# mimxrt10xx.net
KiCad netlist of a schematic drawn in Altium Designer
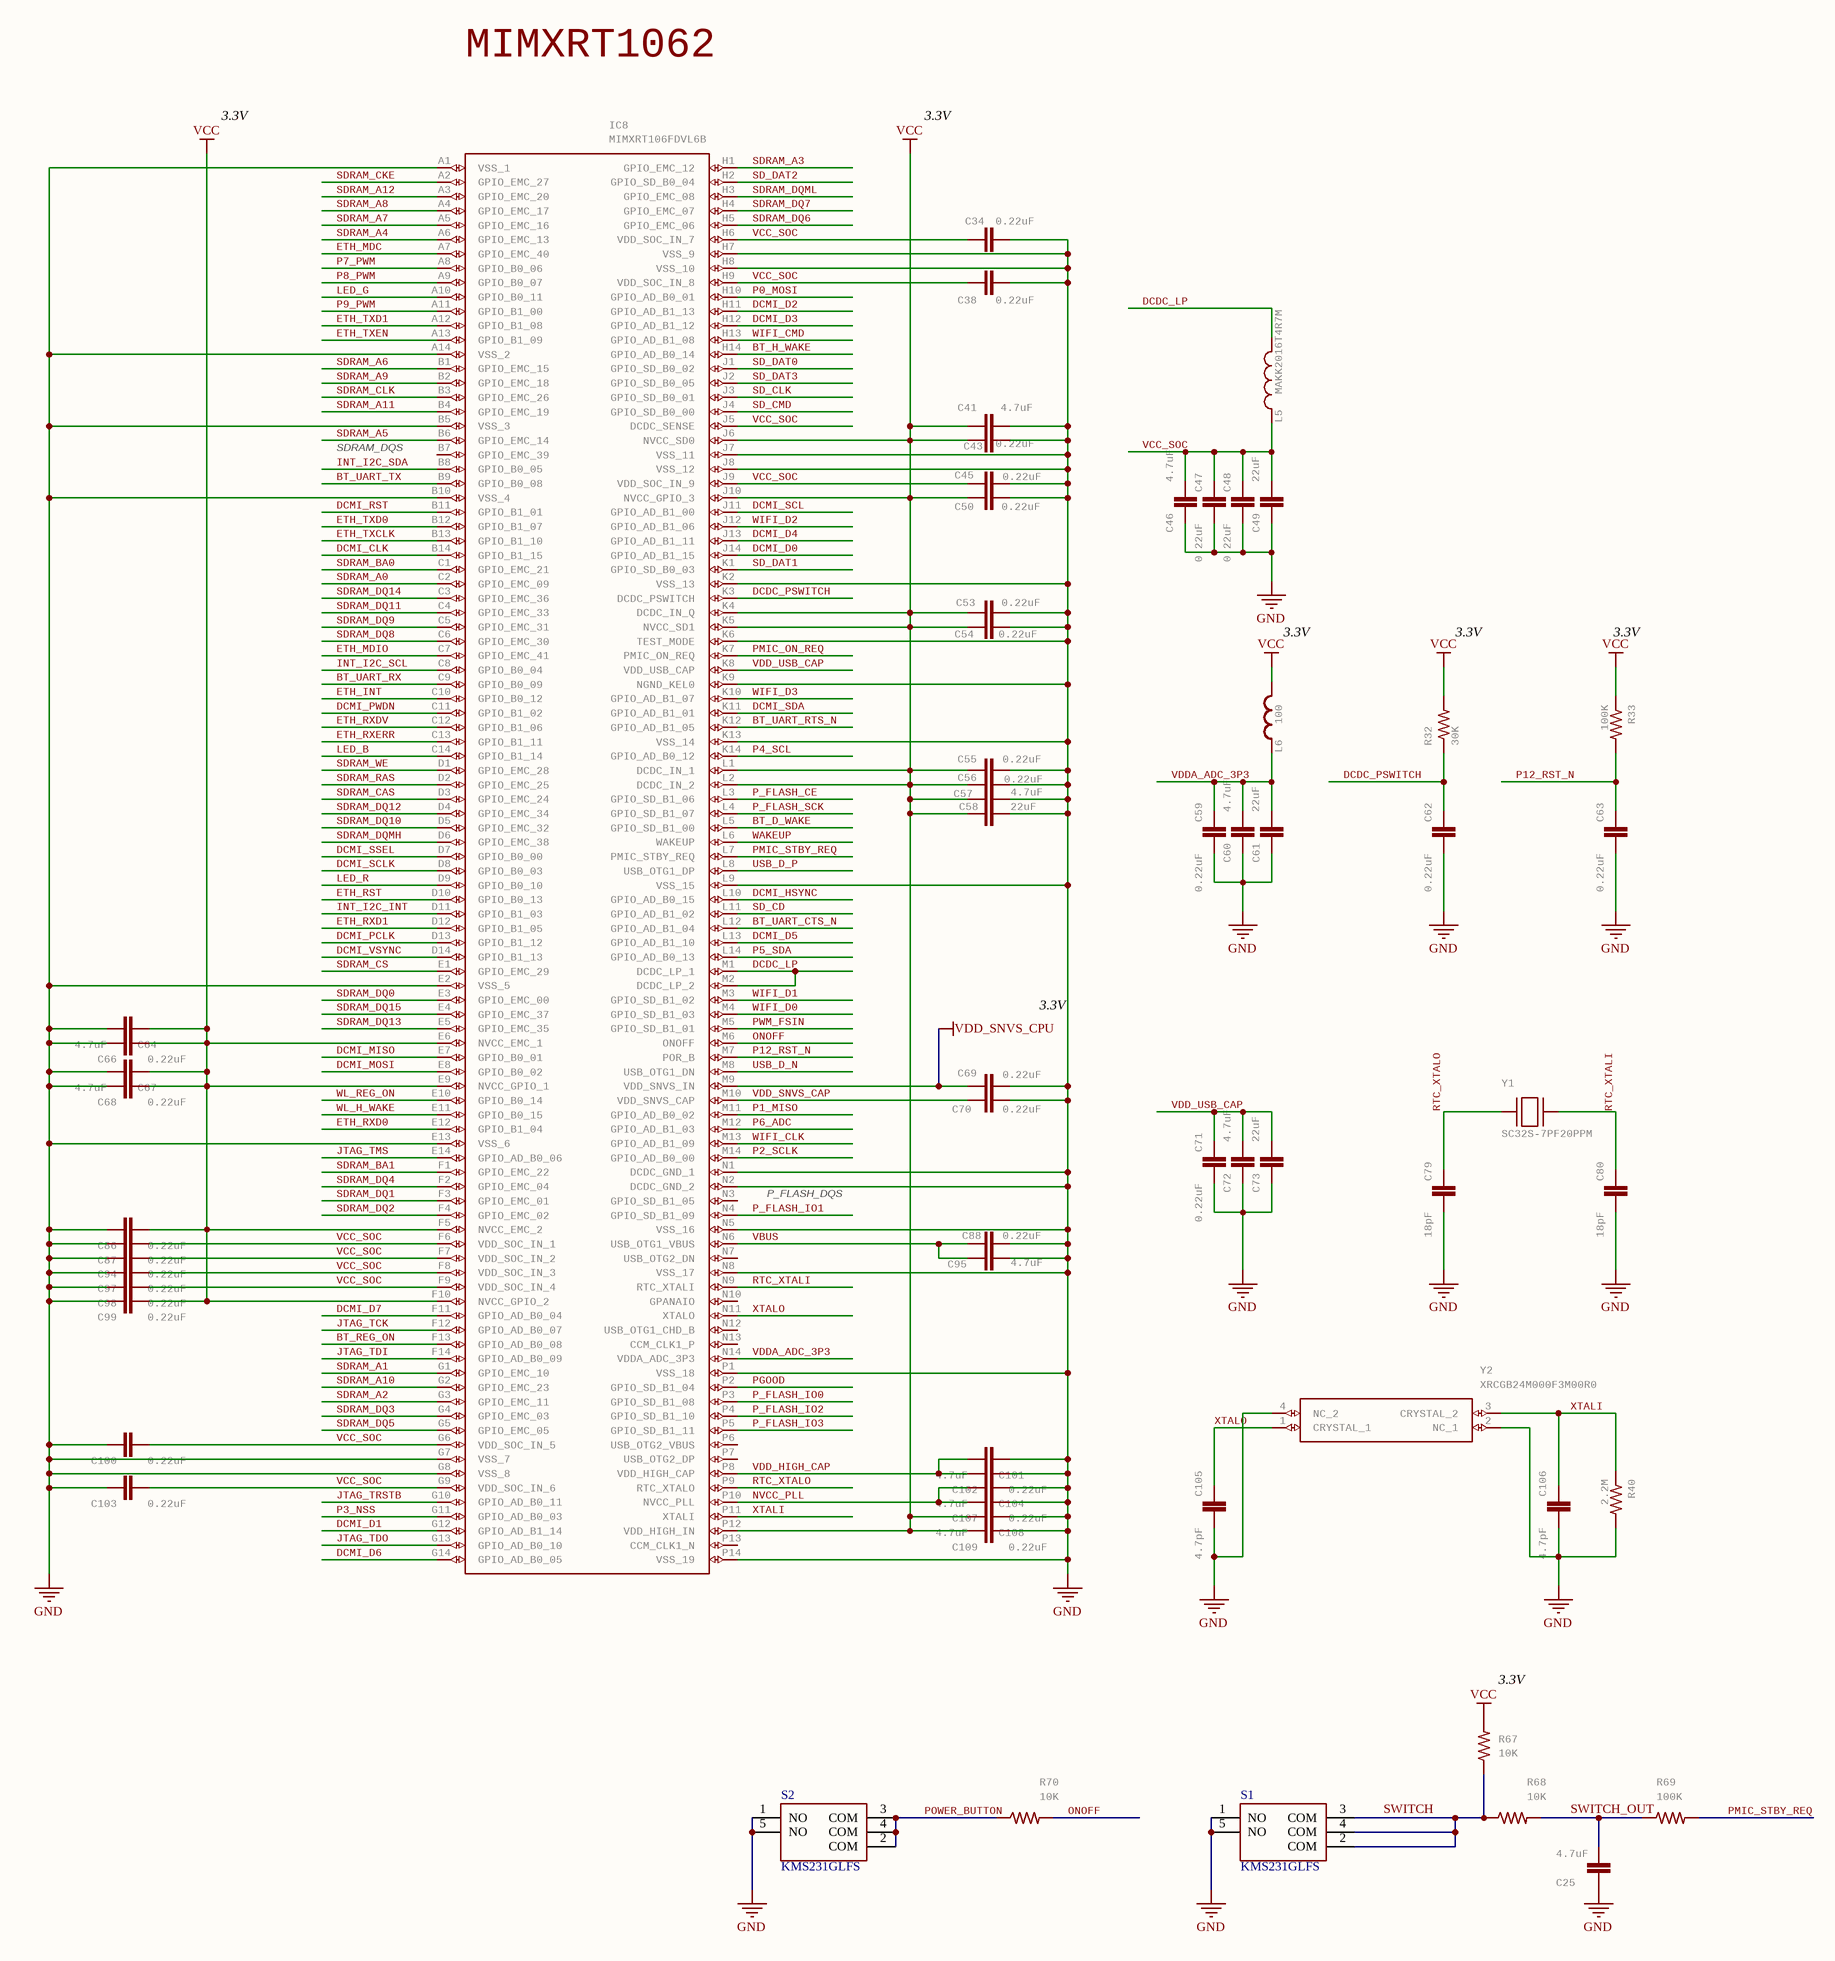
[diagram p0: mimxrt10xx.SchDoc]

(export (version "E")
  (design (tool "Eeschema 10.0.6"))
  (components
    (comp (ref "C25")
      (value "4.7uF")
      (footprint "0402-CAP")
      (description "CapacitorStandard 0603 ceramic capacitor, and 0.1\" leaded capacitor.")
      (fields (field (name "MPN") "JMK105BBJ475MV-F"))
      (libsource (lib "rt10") (part "CAP0402-CAP"))
    )
    (comp (ref "C34")
      (value "0.22uF")
      (footprint "C0201")
      (description "CAPACITOR, European symbol")
      (fields (field (name "MPN") "GRM033R60J224ME15D"))
      (libsource (lib "rt10") (part "C-EUC0201"))
    )
    (comp (ref "C38")
      (value "0.22uF")
      (footprint "C0201")
      (description "CAPACITOR, European symbol")
      (fields (field (name "MPN") "GRM033R60J224ME15D"))
      (libsource (lib "rt10") (part "C-EUC0201"))
    )
    (comp (ref "C41")
      (value "4.7uF")
      (footprint "0402-CAP")
      (description "CapacitorStandard 0603 ceramic capacitor, and 0.1\" leaded capacitor.")
      (fields (field (name "MPN") "JMK105BBJ475MV-F"))
      (libsource (lib "") (part "CAP0402-CAP_1"))
    )
    (comp (ref "C43")
      (value "0.22uF")
      (footprint "C0201")
      (description "CAPACITOR, European symbol")
      (fields (field (name "MPN") "GRM033R60J224ME15D"))
      (libsource (lib "rt10") (part "C-EUC0201"))
    )
    (comp (ref "C45")
      (value "0.22uF")
      (footprint "C0201")
      (description "CAPACITOR, European symbol")
      (fields (field (name "MPN") "GRM033R60J224ME15D"))
      (libsource (lib "rt10") (part "C-EUC0201"))
    )
    (comp (ref "C46")
      (value "4.7uF")
      (footprint "0402-CAP")
      (description "CapacitorStandard 0603 ceramic capacitor, and 0.1\" leaded capacitor.")
      (fields (field (name "MPN") "JMK105BBJ475MV-F"))
      (libsource (lib "rt10") (part "CAP0402-CAP"))
    )
    (comp (ref "C47")
      (value "0.22uF")
      (footprint "C0201")
      (description "CAPACITOR, European symbol")
      (fields (field (name "MPN") "GRM033R60J224ME15D"))
      (libsource (lib "") (part "C-EUC0201_1"))
    )
    (comp (ref "C48")
      (value "0.22uF")
      (footprint "C0201")
      (description "CAPACITOR, European symbol")
      (fields (field (name "MPN") "GRM033R60J224ME15D"))
      (libsource (lib "") (part "C-EUC0201_1"))
    )
    (comp (ref "C49")
      (value "22uF")
      (footprint "0805")
      (fields (field (name "MPN") "CL21A226MQQNNNE"))
      (libsource (lib "rt10") (part "22UF-0805-6.3V-20%"))
    )
    (comp (ref "C50")
      (value "0.22uF")
      (footprint "C0201")
      (description "CAPACITOR, European symbol")
      (fields (field (name "MPN") "GRM033R60J224ME15D"))
      (libsource (lib "rt10") (part "C-EUC0201"))
    )
    (comp (ref "C53")
      (value "0.22uF")
      (footprint "C0201")
      (description "CAPACITOR, European symbol")
      (fields (field (name "MPN") "GRM033R60J224ME15D"))
      (libsource (lib "rt10") (part "C-EUC0201"))
    )
    (comp (ref "C54")
      (value "0.22uF")
      (footprint "C0201")
      (description "CAPACITOR, European symbol")
      (fields (field (name "MPN") "GRM033R60J224ME15D"))
      (libsource (lib "rt10") (part "C-EUC0201"))
    )
    (comp (ref "C55")
      (value "0.22uF")
      (footprint "C0201")
      (description "CAPACITOR, European symbol")
      (fields (field (name "MPN") "GRM033R60J224ME15D"))
      (libsource (lib "rt10") (part "C-EUC0201"))
    )
    (comp (ref "C56")
      (value "0.22uF")
      (footprint "C0201")
      (description "CAPACITOR, European symbol")
      (fields (field (name "MPN") "GRM033R60J224ME15D"))
      (libsource (lib "rt10") (part "C-EUC0201"))
    )
    (comp (ref "C57")
      (value "4.7uF")
      (footprint "0402-CAP")
      (description "CapacitorStandard 0603 ceramic capacitor, and 0.1\" leaded capacitor.")
      (fields (field (name "MPN") "JMK105BBJ475MV-F"))
      (libsource (lib "") (part "CAP0402-CAP_1"))
    )
    (comp (ref "C58")
      (value "22uF")
      (footprint "0805")
      (fields (field (name "MPN") "CL21A226MQQNNNE"))
      (libsource (lib "") (part "22UF-0805-6.3V-20%_1"))
    )
    (comp (ref "C59")
      (value "0.22uF")
      (footprint "C0201")
      (description "CAPACITOR, European symbol")
      (fields (field (name "MPN") "GRM033R60J224ME15D"))
      (libsource (lib "") (part "C-EUC0201_1"))
    )
    (comp (ref "C60")
      (value "4.7uF")
      (footprint "0402-CAP")
      (description "CapacitorStandard 0603 ceramic capacitor, and 0.1\" leaded capacitor.")
      (fields (field (name "MPN") "JMK105BBJ475MV-F"))
      (libsource (lib "rt10") (part "CAP0402-CAP"))
    )
    (comp (ref "C61")
      (value "22uF")
      (footprint "0805")
      (fields (field (name "MPN") "CL21A226MQQNNNE"))
      (libsource (lib "rt10") (part "22UF-0805-6.3V-20%"))
    )
    (comp (ref "C62")
      (value "0.22uF")
      (footprint "C0201")
      (description "CAPACITOR, European symbol")
      (fields (field (name "MPN") "GRM033R60J224ME15D"))
      (libsource (lib "") (part "C-EUC0201_1"))
    )
    (comp (ref "C63")
      (value "0.22uF")
      (footprint "C0201")
      (description "CAPACITOR, European symbol")
      (fields (field (name "MPN") "GRM033R60J224ME15D"))
      (libsource (lib "") (part "C-EUC0201_1"))
    )
    (comp (ref "C64")
      (value "4.7uF")
      (footprint "0402-CAP")
      (description "CapacitorStandard 0603 ceramic capacitor, and 0.1\" leaded capacitor.")
      (fields (field (name "MPN") "JMK105BBJ475MV-F"))
      (libsource (lib "") (part "CAP0402-CAP_1"))
    )
    (comp (ref "C66")
      (value "0.22uF")
      (footprint "C0201")
      (description "CAPACITOR, European symbol")
      (fields (field (name "MPN") "GRM033R60J224ME15D"))
      (libsource (lib "rt10") (part "C-EUC0201"))
    )
    (comp (ref "C67")
      (value "4.7uF")
      (footprint "0402-CAP")
      (description "CapacitorStandard 0603 ceramic capacitor, and 0.1\" leaded capacitor.")
      (fields (field (name "MPN") "JMK105BBJ475MV-F"))
      (libsource (lib "") (part "CAP0402-CAP_1"))
    )
    (comp (ref "C68")
      (value "0.22uF")
      (footprint "C0201")
      (description "CAPACITOR, European symbol")
      (fields (field (name "MPN") "GRM033R60J224ME15D"))
      (libsource (lib "rt10") (part "C-EUC0201"))
    )
    (comp (ref "C69")
      (value "0.22uF")
      (footprint "C0201")
      (description "CAPACITOR, European symbol")
      (fields (field (name "MPN") "GRM033R60J224ME15D"))
      (libsource (lib "rt10") (part "C-EUC0201"))
    )
    (comp (ref "C70")
      (value "0.22uF")
      (footprint "C0201")
      (description "CAPACITOR, European symbol")
      (fields (field (name "MPN") "GRM033R60J224ME15D"))
      (libsource (lib "rt10") (part "C-EUC0201"))
    )
    (comp (ref "C71")
      (value "0.22uF")
      (footprint "C0201")
      (description "CAPACITOR, European symbol")
      (fields (field (name "MPN") "GRM033R60J224ME15D"))
      (libsource (lib "") (part "C-EUC0201_1"))
    )
    (comp (ref "C72")
      (value "4.7uF")
      (footprint "0402-CAP")
      (description "CapacitorStandard 0603 ceramic capacitor, and 0.1\" leaded capacitor.")
      (fields (field (name "MPN") "JMK105BBJ475MV-F"))
      (libsource (lib "rt10") (part "CAP0402-CAP"))
    )
    (comp (ref "C73")
      (value "22uF")
      (footprint "0805")
      (fields (field (name "MPN") "CL21A226MQQNNNE"))
      (libsource (lib "rt10") (part "22UF-0805-6.3V-20%"))
    )
    (comp (ref "C79")
      (value "18pF")
      (footprint "C0201")
      (description "CAPACITOR, European symbol")
      (fields (field (name "MPN") "GRM0335C1E180JA01D"))
      (libsource (lib "") (part "C-EUC0201_1"))
    )
    (comp (ref "C80")
      (value "18pF")
      (footprint "C0201")
      (description "CAPACITOR, European symbol")
      (fields (field (name "MPN") "GRM0335C1E180JA01D"))
      (libsource (lib "") (part "C-EUC0201_1"))
    )
    (comp (ref "C86")
      (value "0.22uF")
      (footprint "C0201")
      (description "CAPACITOR, European symbol")
      (fields (field (name "MPN") "GRM033R60J224ME15D"))
      (libsource (lib "rt10") (part "C-EUC0201"))
    )
    (comp (ref "C87")
      (value "0.22uF")
      (footprint "C0201")
      (description "CAPACITOR, European symbol")
      (fields (field (name "MPN") "GRM033R60J224ME15D"))
      (libsource (lib "rt10") (part "C-EUC0201"))
    )
    (comp (ref "C88")
      (value "0.22uF")
      (footprint "C0201")
      (description "CAPACITOR, European symbol")
      (fields (field (name "MPN") "GRM033R60J224ME15D"))
      (libsource (lib "rt10") (part "C-EUC0201"))
    )
    (comp (ref "C94")
      (value "0.22uF")
      (footprint "C0201")
      (description "CAPACITOR, European symbol")
      (fields (field (name "MPN") "GRM033R60J224ME15D"))
      (libsource (lib "rt10") (part "C-EUC0201"))
    )
    (comp (ref "C95")
      (value "4.7uF")
      (footprint "0402-CAP")
      (description "CapacitorStandard 0603 ceramic capacitor, and 0.1\" leaded capacitor.")
      (fields (field (name "MPN") "JMK105BBJ475MV-F"))
      (libsource (lib "") (part "CAP0402-CAP_1"))
    )
    (comp (ref "C97")
      (value "0.22uF")
      (footprint "C0201")
      (description "CAPACITOR, European symbol")
      (fields (field (name "MPN") "GRM033R60J224ME15D"))
      (libsource (lib "rt10") (part "C-EUC0201"))
    )
    (comp (ref "C98")
      (value "0.22uF")
      (footprint "C0201")
      (description "CAPACITOR, European symbol")
      (fields (field (name "MPN") "GRM033R60J224ME15D"))
      (libsource (lib "rt10") (part "C-EUC0201"))
    )
    (comp (ref "C99")
      (value "0.22uF")
      (footprint "C0201")
      (description "CAPACITOR, European symbol")
      (fields (field (name "MPN") "GRM033R60J224ME15D"))
      (libsource (lib "rt10") (part "C-EUC0201"))
    )
    (comp (ref "C100")
      (value "0.22uF")
      (footprint "C0201")
      (description "CAPACITOR, European symbol")
      (fields (field (name "MPN") "GRM033R60J224ME15D"))
      (libsource (lib "rt10") (part "C-EUC0201"))
    )
    (comp (ref "C101")
      (value "4.7uF")
      (footprint "0402-CAP")
      (description "CapacitorStandard 0603 ceramic capacitor, and 0.1\" leaded capacitor.")
      (fields (field (name "MPN") "JMK105BBJ475MV-F"))
      (libsource (lib "") (part "CAP0402-CAP_1"))
    )
    (comp (ref "C102")
      (value "0.22uF")
      (footprint "C0201")
      (description "CAPACITOR, European symbol")
      (fields (field (name "MPN") "GRM033R60J224ME15D"))
      (libsource (lib "rt10") (part "C-EUC0201"))
    )
    (comp (ref "C103")
      (value "0.22uF")
      (footprint "C0201")
      (description "CAPACITOR, European symbol")
      (fields (field (name "MPN") "GRM033R60J224ME15D"))
      (libsource (lib "rt10") (part "C-EUC0201"))
    )
    (comp (ref "C104")
      (value "4.7uF")
      (footprint "0402-CAP")
      (description "CapacitorStandard 0603 ceramic capacitor, and 0.1\" leaded capacitor.")
      (fields (field (name "MPN") "JMK105BBJ475MV-F"))
      (libsource (lib "") (part "CAP0402-CAP_1"))
    )
    (comp (ref "C105")
      (value "4.7pF")
      (footprint "C0201")
      (description "CAPACITOR, European symbol")
      (fields (field (name "MPN") "GRM0335C1E4R7CA01D"))
      (libsource (lib "") (part "C-EUC0201_1"))
    )
    (comp (ref "C106")
      (value "4.7pF")
      (footprint "C0201")
      (description "CAPACITOR, European symbol")
      (fields (field (name "MPN") "GRM0335C1E4R7CA01D"))
      (libsource (lib "") (part "C-EUC0201_1"))
    )
    (comp (ref "C107")
      (value "0.22uF")
      (footprint "C0201")
      (description "CAPACITOR, European symbol")
      (fields (field (name "MPN") "GRM033R60J224ME15D"))
      (libsource (lib "rt10") (part "C-EUC0201"))
    )
    (comp (ref "C108")
      (value "4.7uF")
      (footprint "0402-CAP")
      (description "CapacitorStandard 0603 ceramic capacitor, and 0.1\" leaded capacitor.")
      (fields (field (name "MPN") "JMK105BBJ475MV-F"))
      (libsource (lib "") (part "CAP0402-CAP_1"))
    )
    (comp (ref "C109")
      (value "0.22uF")
      (footprint "C0201")
      (description "CAPACITOR, European symbol")
      (fields (field (name "MPN") "GRM033R60J224ME15D"))
      (libsource (lib "rt10") (part "C-EUC0201"))
    )
    (comp (ref "IC8")
      (value "MIMXRT106FDVL6B")
      (footprint "BGA196C65P14X14_1000X1000X143")
      (libsource (lib "rt10") (part "MIMXRT1052DVL6B"))
    )
    (comp (ref "L5")
      (value "MAKK2016T4R7M")
      (footprint "INDC2016X100N")
      (description "INDUCTOR, METAL CORE, SHIELDED, SMD HIGH CURRENT, 4.7uH, 20%, TR Check availability")
      (fields (field (name "MF") "Taiyo Yuden"))
      (libsource (lib "rt10") (part "MAKK2016T4R7M"))
    )
    (comp (ref "L6")
      (value "100")
      (footprint "C0402")
      (fields (field (name "MPN") "MFBM1V1005-101-R"))
      (libsource (lib "rt10") (part "INDUCTOR0402"))
    )
    (comp (ref "R32")
      (value "30K")
      (footprint "0201-RES")
      (description "ResistorBasic schematic elements and footprints for 0603, 1206, and PTH resistors.")
      (fields (field (name "MPN") "RC0201FR-0730KL"))
      (libsource (lib "rt10") (part "RESISTOR0402-RES"))
    )
    (comp (ref "R33")
      (value "100K")
      (footprint "0402-RES")
      (description "ResistorBasic schematic elements and footprints for 0603, 1206, and PTH resistors.")
      (fields (field (name "MPN") "AC0402FR-07100KL"))
      (libsource (lib "rt10") (part "RESISTOR0402-RES"))
    )
    (comp (ref "R40")
      (value "2.2M")
      (footprint "0402-RES")
      (description "ResistorBasic schematic elements and footprints for 0603, 1206, and PTH resistors.")
      (fields (field (name "MPN") "RC0402FR-072M2L"))
      (libsource (lib "rt10") (part "RESISTOR0402-RES"))
    )
    (comp (ref "R67")
      (value "10K")
      (footprint "0402-RES")
      (description "ResistorBasic schematic elements and footprints for 0603, 1206, and PTH resistors.")
      (fields (field (name "MPN") "AC0402FR-1310K"))
      (libsource (lib "rt10") (part "RESISTOR0402-RES"))
    )
    (comp (ref "R68")
      (value "10K")
      (footprint "0402-RES")
      (description "ResistorBasic schematic elements and footprints for 0603, 1206, and PTH resistors.")
      (fields (field (name "MPN") "AC0402FR-1310K"))
      (libsource (lib "rt10") (part "RESISTOR0402-RES"))
    )
    (comp (ref "R69")
      (value "100K")
      (footprint "0402-RES")
      (description "ResistorBasic schematic elements and footprints for 0603, 1206, and PTH resistors.")
      (fields (field (name "MPN") "AC0402FR-07100KL"))
      (libsource (lib "rt10") (part "RESISTOR0402-RES"))
    )
    (comp (ref "R70")
      (value "10K")
      (footprint "0402-RES")
      (description "ResistorBasic schematic elements and footprints for 0603, 1206, and PTH resistors.")
      (fields (field (name "MPN") "AC0402FR-1310K"))
      (libsource (lib "rt10") (part "RESISTOR0402-RES"))
    )
    (comp (ref "S1")
      (value "KMS231GLFS")
      (footprint "KMS231GLFS")
      (libsource (lib "rt10") (part "KMS231GLFS"))
    )
    (comp (ref "S2")
      (value "KMS231GLFS")
      (footprint "KMS231GLFS")
      (libsource (lib "rt10") (part "KMS231GLFS"))
    )
    (comp (ref "Y1")
      (value "SC32S-7PF20PPM")
      (footprint "XTAL_ABS07-32.768KHZ-7-T")
      (description "Check availability")
      (fields (field (name "MF") "Abracon") (field (name "MP") "ABS07-32.768KHZ-7-T"))
      (libsource (lib "rt10") (part "ABS07-32.768KHZ-7-T"))
    )
    (comp (ref "Y2")
      (value "XRCGB24M000F3M00R0")
      (footprint "XRCGB24M000F3M00R0")
      (description "Murata 24MHz Crystal +/-30ppm SMD 4-Pin 2 x 1.6 x 0.7mm   Source:  Datasheet")
      (fields (field (name "MOUSER_PART_NUMBER") "81-XRCGB24M000F3M0R0"))
      (libsource (lib "rt10") (part "XRCGB24M000F3M00R0"))
    )
  )
  (nets
    (net (code "1") (name "/BT_D_WAKE") (class "Default")
      (node (ref "IC8") (pin "L5") (pinfunction "GPIO_SD_B1_00_L5") (pintype "bidirectional"))
    )
    (net (code "2") (name "/BT_H_WAKE") (class "Default")
      (node (ref "IC8") (pin "H14") (pinfunction "GPIO_AD_B0_14_H14") (pintype "bidirectional"))
    )
    (net (code "3") (name "/BT_REG_ON") (class "Default")
      (node (ref "IC8") (pin "F13") (pinfunction "GPIO_AD_B0_08_F13") (pintype "bidirectional"))
    )
    (net (code "4") (name "/BT_UART_CTS_N") (class "Default")
      (node (ref "IC8") (pin "L12") (pinfunction "GPIO_AD_B1_04_L12") (pintype "bidirectional"))
    )
    (net (code "5") (name "/BT_UART_RTS_N") (class "Default")
      (node (ref "IC8") (pin "K12") (pinfunction "GPIO_AD_B1_05_K12") (pintype "bidirectional"))
    )
    (net (code "6") (name "/BT_UART_RX") (class "Default")
      (node (ref "IC8") (pin "C9") (pinfunction "GPIO_B0_09_C9") (pintype "bidirectional"))
    )
    (net (code "7") (name "/BT_UART_TX") (class "Default")
      (node (ref "IC8") (pin "B9") (pinfunction "GPIO_B0_08_B9") (pintype "bidirectional"))
    )
    (net (code "8") (name "/DCDC_LP") (class "Default")
      (node (ref "IC8") (pin "M1") (pinfunction "DCDC_LP_1_M1") (pintype "bidirectional"))
      (node (ref "IC8") (pin "M2") (pinfunction "DCDC_LP_2_M2") (pintype "bidirectional"))
      (node (ref "L5") (pin "2") (pinfunction "2_2") (pintype "passive"))
    )
    (net (code "9") (name "/DCDC_PSWITCH") (class "Default")
      (node (ref "C62") (pin "1") (pinfunction "1_1") (pintype "passive"))
      (node (ref "IC8") (pin "K3") (pinfunction "DCDC_PSWITCH_K3") (pintype "bidirectional"))
      (node (ref "R32") (pin "1") (pinfunction "1_1") (pintype "passive"))
    )
    (net (code "10") (name "/DCMI_CLK") (class "Default")
      (node (ref "IC8") (pin "B14") (pinfunction "GPIO_B1_15_B14") (pintype "bidirectional"))
    )
    (net (code "11") (name "/DCMI_D0") (class "Default")
      (node (ref "IC8") (pin "J14") (pinfunction "GPIO_AD_B1_15_J14") (pintype "bidirectional"))
    )
    (net (code "12") (name "/DCMI_D1") (class "Default")
      (node (ref "IC8") (pin "G12") (pinfunction "GPIO_AD_B1_14_G12") (pintype "bidirectional"))
    )
    (net (code "13") (name "/DCMI_D2") (class "Default")
      (node (ref "IC8") (pin "H11") (pinfunction "GPIO_AD_B1_13_H11") (pintype "bidirectional"))
    )
    (net (code "14") (name "/DCMI_D3") (class "Default")
      (node (ref "IC8") (pin "H12") (pinfunction "GPIO_AD_B1_12_H12") (pintype "bidirectional"))
    )
    (net (code "15") (name "/DCMI_D4") (class "Default")
      (node (ref "IC8") (pin "J13") (pinfunction "GPIO_AD_B1_11_J13") (pintype "bidirectional"))
    )
    (net (code "16") (name "/DCMI_D5") (class "Default")
      (node (ref "IC8") (pin "L13") (pinfunction "GPIO_AD_B1_10_L13") (pintype "bidirectional"))
    )
    (net (code "17") (name "/DCMI_D6") (class "Default")
      (node (ref "IC8") (pin "G14") (pinfunction "GPIO_AD_B0_05_G14") (pintype "bidirectional"))
    )
    (net (code "18") (name "/DCMI_D7") (class "Default")
      (node (ref "IC8") (pin "F11") (pinfunction "GPIO_AD_B0_04_F11") (pintype "bidirectional"))
    )
    (net (code "19") (name "/DCMI_HSYNC") (class "Default")
      (node (ref "IC8") (pin "L10") (pinfunction "GPIO_AD_B0_15_L10") (pintype "bidirectional"))
    )
    (net (code "20") (name "/DCMI_MISO") (class "Default")
      (node (ref "IC8") (pin "E7") (pinfunction "GPIO_B0_01_E7") (pintype "bidirectional"))
    )
    (net (code "21") (name "/DCMI_MOSI") (class "Default")
      (node (ref "IC8") (pin "E8") (pinfunction "GPIO_B0_02_E8") (pintype "bidirectional"))
    )
    (net (code "22") (name "/DCMI_PCLK") (class "Default")
      (node (ref "IC8") (pin "D13") (pinfunction "GPIO_B1_12_D13") (pintype "bidirectional"))
    )
    (net (code "23") (name "/DCMI_PWDN") (class "Default")
      (node (ref "IC8") (pin "C11") (pinfunction "GPIO_B1_02_C11") (pintype "bidirectional"))
    )
    (net (code "24") (name "/DCMI_RST") (class "Default")
      (node (ref "IC8") (pin "B11") (pinfunction "GPIO_B1_01_B11") (pintype "bidirectional"))
    )
    (net (code "25") (name "/DCMI_SCL") (class "Default")
      (node (ref "IC8") (pin "J11") (pinfunction "GPIO_AD_B1_00_J11") (pintype "bidirectional"))
    )
    (net (code "26") (name "/DCMI_SCLK") (class "Default")
      (node (ref "IC8") (pin "D8") (pinfunction "GPIO_B0_03_D8") (pintype "bidirectional"))
    )
    (net (code "27") (name "/DCMI_SDA") (class "Default")
      (node (ref "IC8") (pin "K11") (pinfunction "GPIO_AD_B1_01_K11") (pintype "bidirectional"))
    )
    (net (code "28") (name "/DCMI_SSEL") (class "Default")
      (node (ref "IC8") (pin "D7") (pinfunction "GPIO_B0_00_D7") (pintype "bidirectional"))
    )
    (net (code "29") (name "/DCMI_VSYNC") (class "Default")
      (node (ref "IC8") (pin "D14") (pinfunction "GPIO_B1_13_D14") (pintype "bidirectional"))
    )
    (net (code "30") (name "/ETH_INT") (class "Default")
      (node (ref "IC8") (pin "C10") (pinfunction "GPIO_B0_12_C10") (pintype "bidirectional"))
    )
    (net (code "31") (name "/ETH_MDC") (class "Default")
      (node (ref "IC8") (pin "A7") (pinfunction "GPIO_EMC_40_A7") (pintype "bidirectional"))
    )
    (net (code "32") (name "/ETH_MDIO") (class "Default")
      (node (ref "IC8") (pin "C7") (pinfunction "GPIO_EMC_41_C7") (pintype "bidirectional"))
    )
    (net (code "33") (name "/ETH_RST") (class "Default")
      (node (ref "IC8") (pin "D10") (pinfunction "GPIO_B0_13_D10") (pintype "bidirectional"))
    )
    (net (code "34") (name "/ETH_RXD0") (class "Default")
      (node (ref "IC8") (pin "E12") (pinfunction "GPIO_B1_04_E12") (pintype "bidirectional"))
    )
    (net (code "35") (name "/ETH_RXD1") (class "Default")
      (node (ref "IC8") (pin "D12") (pinfunction "GPIO_B1_05_D12") (pintype "bidirectional"))
    )
    (net (code "36") (name "/ETH_RXDV") (class "Default")
      (node (ref "IC8") (pin "C12") (pinfunction "GPIO_B1_06_C12") (pintype "bidirectional"))
    )
    (net (code "37") (name "/ETH_RXERR") (class "Default")
      (node (ref "IC8") (pin "C13") (pinfunction "GPIO_B1_11_C13") (pintype "bidirectional"))
    )
    (net (code "38") (name "/ETH_TXCLK") (class "Default")
      (node (ref "IC8") (pin "B13") (pinfunction "GPIO_B1_10_B13") (pintype "bidirectional"))
    )
    (net (code "39") (name "/ETH_TXD0") (class "Default")
      (node (ref "IC8") (pin "B12") (pinfunction "GPIO_B1_07_B12") (pintype "bidirectional"))
    )
    (net (code "40") (name "/ETH_TXD1") (class "Default")
      (node (ref "IC8") (pin "A12") (pinfunction "GPIO_B1_08_A12") (pintype "bidirectional"))
    )
    (net (code "41") (name "/ETH_TXEN") (class "Default")
      (node (ref "IC8") (pin "A13") (pinfunction "GPIO_B1_09_A13") (pintype "bidirectional"))
    )
    (net (code "42") (name "/INT_I2C_INT") (class "Default")
      (node (ref "IC8") (pin "D11") (pinfunction "GPIO_B1_03_D11") (pintype "bidirectional"))
    )
    (net (code "43") (name "/INT_I2C_SCL") (class "Default")
      (node (ref "IC8") (pin "C8") (pinfunction "GPIO_B0_04_C8") (pintype "bidirectional"))
    )
    (net (code "44") (name "/INT_I2C_SDA") (class "Default")
      (node (ref "IC8") (pin "B8") (pinfunction "GPIO_B0_05_B8") (pintype "bidirectional"))
    )
    (net (code "45") (name "/JTAG_TCK") (class "Default")
      (node (ref "IC8") (pin "F12") (pinfunction "GPIO_AD_B0_07_F12") (pintype "bidirectional"))
    )
    (net (code "46") (name "/JTAG_TDI") (class "Default")
      (node (ref "IC8") (pin "F14") (pinfunction "GPIO_AD_B0_09_F14") (pintype "bidirectional"))
    )
    (net (code "47") (name "/JTAG_TDO") (class "Default")
      (node (ref "IC8") (pin "G13") (pinfunction "GPIO_AD_B0_10_G13") (pintype "bidirectional"))
    )
    (net (code "48") (name "/JTAG_TMS") (class "Default")
      (node (ref "IC8") (pin "E14") (pinfunction "GPIO_AD_B0_06_E14") (pintype "bidirectional"))
    )
    (net (code "49") (name "/JTAG_TRSTB") (class "Default")
      (node (ref "IC8") (pin "G10") (pinfunction "GPIO_AD_B0_11_G10") (pintype "bidirectional"))
    )
    (net (code "50") (name "/LED_B") (class "Default")
      (node (ref "IC8") (pin "C14") (pinfunction "GPIO_B1_14_C14") (pintype "bidirectional"))
    )
    (net (code "51") (name "/LED_G") (class "Default")
      (node (ref "IC8") (pin "A10") (pinfunction "GPIO_B0_11_A10") (pintype "bidirectional"))
    )
    (net (code "52") (name "/LED_R") (class "Default")
      (node (ref "IC8") (pin "D9") (pinfunction "GPIO_B0_10_D9") (pintype "bidirectional"))
    )
    (net (code "53") (name "/NVCC_PLL") (class "Default")
      (node (ref "C104") (pin "2") (pinfunction "2_2") (pintype "passive"))
      (node (ref "C107") (pin "1") (pinfunction "1_1") (pintype "passive"))
      (node (ref "IC8") (pin "P10") (pinfunction "NVCC_PLL_P10") (pintype "bidirectional"))
    )
    (net (code "54") (name "/ONOFF") (class "Default")
      (node (ref "IC8") (pin "M6") (pinfunction "ONOFF_M6") (pintype "bidirectional"))
      (node (ref "R70") (pin "2") (pinfunction "2_2") (pintype "passive"))
    )
    (net (code "55") (name "/P0_MOSI") (class "Default")
      (node (ref "IC8") (pin "H10") (pinfunction "GPIO_AD_B0_01_H10") (pintype "bidirectional"))
    )
    (net (code "56") (name "/P1_MISO") (class "Default")
      (node (ref "IC8") (pin "M11") (pinfunction "GPIO_AD_B0_02_M11") (pintype "bidirectional"))
    )
    (net (code "57") (name "/P2_SCLK") (class "Default")
      (node (ref "IC8") (pin "M14") (pinfunction "GPIO_AD_B0_00_M14") (pintype "bidirectional"))
    )
    (net (code "58") (name "/P3_NSS") (class "Default")
      (node (ref "IC8") (pin "G11") (pinfunction "GPIO_AD_B0_03_G11") (pintype "bidirectional"))
    )
    (net (code "59") (name "/P4_SCL") (class "Default")
      (node (ref "IC8") (pin "K14") (pinfunction "GPIO_AD_B0_12_K14") (pintype "bidirectional"))
    )
    (net (code "60") (name "/P5_SDA") (class "Default")
      (node (ref "IC8") (pin "L14") (pinfunction "GPIO_AD_B0_13_L14") (pintype "bidirectional"))
    )
    (net (code "61") (name "/P6_ADC") (class "Default")
      (node (ref "IC8") (pin "M12") (pinfunction "GPIO_AD_B1_03_M12") (pintype "bidirectional"))
    )
    (net (code "62") (name "/P7_PWM") (class "Default")
      (node (ref "IC8") (pin "A8") (pinfunction "GPIO_B0_06_A8") (pintype "bidirectional"))
    )
    (net (code "63") (name "/P8_PWM") (class "Default")
      (node (ref "IC8") (pin "A9") (pinfunction "GPIO_B0_07_A9") (pintype "bidirectional"))
    )
    (net (code "64") (name "/P9_PWM") (class "Default")
      (node (ref "IC8") (pin "A11") (pinfunction "GPIO_B1_00_A11") (pintype "bidirectional"))
    )
    (net (code "65") (name "/P12_RST_N") (class "Default")
      (node (ref "C63") (pin "1") (pinfunction "1_1") (pintype "passive"))
      (node (ref "IC8") (pin "M7") (pinfunction "POR_B_M7") (pintype "bidirectional"))
      (node (ref "R33") (pin "2") (pinfunction "2_2") (pintype "passive"))
    )
    (net (code "66") (name "/PGOOD") (class "Default")
      (node (ref "IC8") (pin "P2") (pinfunction "GPIO_SD_B1_04_P2") (pintype "bidirectional"))
    )
    (net (code "67") (name "/PMIC_ON_REQ") (class "Default")
      (node (ref "IC8") (pin "K7") (pinfunction "PMIC_ON_REQ_K7") (pintype "bidirectional"))
    )
    (net (code "68") (name "/PMIC_STBY_REQ") (class "Default")
      (node (ref "IC8") (pin "L7") (pinfunction "PMIC_STBY_REQ_L7") (pintype "bidirectional"))
      (node (ref "R69") (pin "2") (pinfunction "2_2") (pintype "passive"))
    )
    (net (code "69") (name "/POWER_BUTTON") (class "Default")
      (node (ref "R70") (pin "1") (pinfunction "1_1") (pintype "passive"))
      (node (ref "S2") (pin "2") (pinfunction "COM_2") (pintype "passive"))
      (node (ref "S2") (pin "3") (pinfunction "COM_3") (pintype "passive"))
      (node (ref "S2") (pin "4") (pinfunction "COM_4") (pintype "passive"))
    )
    (net (code "70") (name "/PWM_FSIN") (class "Default")
      (node (ref "IC8") (pin "M5") (pinfunction "GPIO_SD_B1_01_M5") (pintype "bidirectional"))
    )
    (net (code "71") (name "/P_FLASH_CE") (class "Default")
      (node (ref "IC8") (pin "L3") (pinfunction "GPIO_SD_B1_06_L3") (pintype "bidirectional"))
    )
    (net (code "72") (name "/P_FLASH_IO0") (class "Default")
      (node (ref "IC8") (pin "P3") (pinfunction "GPIO_SD_B1_08_P3") (pintype "bidirectional"))
    )
    (net (code "73") (name "/P_FLASH_IO1") (class "Default")
      (node (ref "IC8") (pin "N4") (pinfunction "GPIO_SD_B1_09_N4") (pintype "bidirectional"))
    )
    (net (code "74") (name "/P_FLASH_IO2") (class "Default")
      (node (ref "IC8") (pin "P4") (pinfunction "GPIO_SD_B1_10_P4") (pintype "bidirectional"))
    )
    (net (code "75") (name "/P_FLASH_IO3") (class "Default")
      (node (ref "IC8") (pin "P5") (pinfunction "GPIO_SD_B1_11_P5") (pintype "bidirectional"))
    )
    (net (code "76") (name "/P_FLASH_SCK") (class "Default")
      (node (ref "IC8") (pin "L4") (pinfunction "GPIO_SD_B1_07_L4") (pintype "bidirectional"))
    )
    (net (code "77") (name "/RTC_XTALI") (class "Default")
      (node (ref "C80") (pin "1") (pinfunction "1_1") (pintype "passive"))
      (node (ref "IC8") (pin "N9") (pinfunction "RTC_XTALI_N9") (pintype "bidirectional"))
      (node (ref "Y1") (pin "2") (pinfunction "2_2") (pintype "passive"))
    )
    (net (code "78") (name "/RTC_XTALO") (class "Default")
      (node (ref "C79") (pin "1") (pinfunction "1_1") (pintype "passive"))
      (node (ref "IC8") (pin "P9") (pinfunction "RTC_XTALO_P9") (pintype "bidirectional"))
      (node (ref "Y1") (pin "1") (pinfunction "1_1") (pintype "passive"))
    )
    (net (code "79") (name "/SDRAM_A0") (class "Default")
      (node (ref "IC8") (pin "C2") (pinfunction "GPIO_EMC_09_C2") (pintype "bidirectional"))
    )
    (net (code "80") (name "/SDRAM_A1") (class "Default")
      (node (ref "IC8") (pin "G1") (pinfunction "GPIO_EMC_10_G1") (pintype "bidirectional"))
    )
    (net (code "81") (name "/SDRAM_A2") (class "Default")
      (node (ref "IC8") (pin "G3") (pinfunction "GPIO_EMC_11_G3") (pintype "bidirectional"))
    )
    (net (code "82") (name "/SDRAM_A3") (class "Default")
      (node (ref "IC8") (pin "H1") (pinfunction "GPIO_EMC_12_H1") (pintype "bidirectional"))
    )
    (net (code "83") (name "/SDRAM_A4") (class "Default")
      (node (ref "IC8") (pin "A6") (pinfunction "GPIO_EMC_13_A6") (pintype "bidirectional"))
    )
    (net (code "84") (name "/SDRAM_A5") (class "Default")
      (node (ref "IC8") (pin "B6") (pinfunction "GPIO_EMC_14_B6") (pintype "bidirectional"))
    )
    (net (code "85") (name "/SDRAM_A6") (class "Default")
      (node (ref "IC8") (pin "B1") (pinfunction "GPIO_EMC_15_B1") (pintype "bidirectional"))
    )
    (net (code "86") (name "/SDRAM_A7") (class "Default")
      (node (ref "IC8") (pin "A5") (pinfunction "GPIO_EMC_16_A5") (pintype "bidirectional"))
    )
    (net (code "87") (name "/SDRAM_A8") (class "Default")
      (node (ref "IC8") (pin "A4") (pinfunction "GPIO_EMC_17_A4") (pintype "bidirectional"))
    )
    (net (code "88") (name "/SDRAM_A9") (class "Default")
      (node (ref "IC8") (pin "B2") (pinfunction "GPIO_EMC_18_B2") (pintype "bidirectional"))
    )
    (net (code "89") (name "/SDRAM_A10") (class "Default")
      (node (ref "IC8") (pin "G2") (pinfunction "GPIO_EMC_23_G2") (pintype "bidirectional"))
    )
    (net (code "90") (name "/SDRAM_A11") (class "Default")
      (node (ref "IC8") (pin "B4") (pinfunction "GPIO_EMC_19_B4") (pintype "bidirectional"))
    )
    (net (code "91") (name "/SDRAM_A12") (class "Default")
      (node (ref "IC8") (pin "A3") (pinfunction "GPIO_EMC_20_A3") (pintype "bidirectional"))
    )
    (net (code "92") (name "/SDRAM_BA0") (class "Default")
      (node (ref "IC8") (pin "C1") (pinfunction "GPIO_EMC_21_C1") (pintype "bidirectional"))
    )
    (net (code "93") (name "/SDRAM_BA1") (class "Default")
      (node (ref "IC8") (pin "F1") (pinfunction "GPIO_EMC_22_F1") (pintype "bidirectional"))
    )
    (net (code "94") (name "/SDRAM_CAS") (class "Default")
      (node (ref "IC8") (pin "D3") (pinfunction "GPIO_EMC_24_D3") (pintype "bidirectional"))
    )
    (net (code "95") (name "/SDRAM_CKE") (class "Default")
      (node (ref "IC8") (pin "A2") (pinfunction "GPIO_EMC_27_A2") (pintype "bidirectional"))
    )
    (net (code "96") (name "/SDRAM_CLK") (class "Default")
      (node (ref "IC8") (pin "B3") (pinfunction "GPIO_EMC_26_B3") (pintype "bidirectional"))
    )
    (net (code "97") (name "/SDRAM_CS") (class "Default")
      (node (ref "IC8") (pin "E1") (pinfunction "GPIO_EMC_29_E1") (pintype "bidirectional"))
    )
    (net (code "98") (name "/SDRAM_DQ0") (class "Default")
      (node (ref "IC8") (pin "E3") (pinfunction "GPIO_EMC_00_E3") (pintype "bidirectional"))
    )
    (net (code "99") (name "/SDRAM_DQ1") (class "Default")
      (node (ref "IC8") (pin "F3") (pinfunction "GPIO_EMC_01_F3") (pintype "bidirectional"))
    )
    (net (code "100") (name "/SDRAM_DQ2") (class "Default")
      (node (ref "IC8") (pin "F4") (pinfunction "GPIO_EMC_02_F4") (pintype "bidirectional"))
    )
    (net (code "101") (name "/SDRAM_DQ3") (class "Default")
      (node (ref "IC8") (pin "G4") (pinfunction "GPIO_EMC_03_G4") (pintype "bidirectional"))
    )
    (net (code "102") (name "/SDRAM_DQ4") (class "Default")
      (node (ref "IC8") (pin "F2") (pinfunction "GPIO_EMC_04_F2") (pintype "bidirectional"))
    )
    (net (code "103") (name "/SDRAM_DQ5") (class "Default")
      (node (ref "IC8") (pin "G5") (pinfunction "GPIO_EMC_05_G5") (pintype "bidirectional"))
    )
    (net (code "104") (name "/SDRAM_DQ6") (class "Default")
      (node (ref "IC8") (pin "H5") (pinfunction "GPIO_EMC_06_H5") (pintype "bidirectional"))
    )
    (net (code "105") (name "/SDRAM_DQ7") (class "Default")
      (node (ref "IC8") (pin "H4") (pinfunction "GPIO_EMC_07_H4") (pintype "bidirectional"))
    )
    (net (code "106") (name "/SDRAM_DQ8") (class "Default")
      (node (ref "IC8") (pin "C6") (pinfunction "GPIO_EMC_30_C6") (pintype "bidirectional"))
    )
    (net (code "107") (name "/SDRAM_DQ9") (class "Default")
      (node (ref "IC8") (pin "C5") (pinfunction "GPIO_EMC_31_C5") (pintype "bidirectional"))
    )
    (net (code "108") (name "/SDRAM_DQ10") (class "Default")
      (node (ref "IC8") (pin "D5") (pinfunction "GPIO_EMC_32_D5") (pintype "bidirectional"))
    )
    (net (code "109") (name "/SDRAM_DQ11") (class "Default")
      (node (ref "IC8") (pin "C4") (pinfunction "GPIO_EMC_33_C4") (pintype "bidirectional"))
    )
    (net (code "110") (name "/SDRAM_DQ12") (class "Default")
      (node (ref "IC8") (pin "D4") (pinfunction "GPIO_EMC_34_D4") (pintype "bidirectional"))
    )
    (net (code "111") (name "/SDRAM_DQ13") (class "Default")
      (node (ref "IC8") (pin "E5") (pinfunction "GPIO_EMC_35_E5") (pintype "bidirectional"))
    )
    (net (code "112") (name "/SDRAM_DQ14") (class "Default")
      (node (ref "IC8") (pin "C3") (pinfunction "GPIO_EMC_36_C3") (pintype "bidirectional"))
    )
    (net (code "113") (name "/SDRAM_DQ15") (class "Default")
      (node (ref "IC8") (pin "E4") (pinfunction "GPIO_EMC_37_E4") (pintype "bidirectional"))
    )
    (net (code "114") (name "/SDRAM_DQMH") (class "Default")
      (node (ref "IC8") (pin "D6") (pinfunction "GPIO_EMC_38_D6") (pintype "bidirectional"))
    )
    (net (code "115") (name "/SDRAM_DQML") (class "Default")
      (node (ref "IC8") (pin "H3") (pinfunction "GPIO_EMC_08_H3") (pintype "bidirectional"))
    )
    (net (code "116") (name "/SDRAM_RAS") (class "Default")
      (node (ref "IC8") (pin "D2") (pinfunction "GPIO_EMC_25_D2") (pintype "bidirectional"))
    )
    (net (code "117") (name "/SDRAM_WE") (class "Default")
      (node (ref "IC8") (pin "D1") (pinfunction "GPIO_EMC_28_D1") (pintype "bidirectional"))
    )
    (net (code "118") (name "/SD_CD") (class "Default")
      (node (ref "IC8") (pin "L11") (pinfunction "GPIO_AD_B1_02_L11") (pintype "bidirectional"))
    )
    (net (code "119") (name "/SD_CLK") (class "Default")
      (node (ref "IC8") (pin "J3") (pinfunction "GPIO_SD_B0_01_J3") (pintype "bidirectional"))
    )
    (net (code "120") (name "/SD_CMD") (class "Default")
      (node (ref "IC8") (pin "J4") (pinfunction "GPIO_SD_B0_00_J4") (pintype "bidirectional"))
    )
    (net (code "121") (name "/SD_DAT0") (class "Default")
      (node (ref "IC8") (pin "J1") (pinfunction "GPIO_SD_B0_02_J1") (pintype "bidirectional"))
    )
    (net (code "122") (name "/SD_DAT1") (class "Default")
      (node (ref "IC8") (pin "K1") (pinfunction "GPIO_SD_B0_03_K1") (pintype "bidirectional"))
    )
    (net (code "123") (name "/SD_DAT2") (class "Default")
      (node (ref "IC8") (pin "H2") (pinfunction "GPIO_SD_B0_04_H2") (pintype "bidirectional"))
    )
    (net (code "124") (name "/SD_DAT3") (class "Default")
      (node (ref "IC8") (pin "J2") (pinfunction "GPIO_SD_B0_05_J2") (pintype "bidirectional"))
    )
    (net (code "125") (name "/SWITCH") (class "Default")
      (node (ref "R67") (pin "1") (pinfunction "1_1") (pintype "passive"))
      (node (ref "R68") (pin "1") (pinfunction "1_1") (pintype "passive"))
      (node (ref "S1") (pin "2") (pinfunction "COM_2") (pintype "passive"))
      (node (ref "S1") (pin "3") (pinfunction "COM_3") (pintype "passive"))
      (node (ref "S1") (pin "4") (pinfunction "COM_4") (pintype "passive"))
    )
    (net (code "126") (name "/SWITCH_OUT") (class "Default")
      (node (ref "C25") (pin "2") (pinfunction "2_2") (pintype "passive"))
      (node (ref "R68") (pin "2") (pinfunction "2_2") (pintype "passive"))
      (node (ref "R69") (pin "1") (pinfunction "1_1") (pintype "passive"))
    )
    (net (code "127") (name "/USB_D_N") (class "Default")
      (node (ref "IC8") (pin "M8") (pinfunction "USB_OTG1_DN_M8") (pintype "bidirectional"))
    )
    (net (code "128") (name "/USB_D_P") (class "Default")
      (node (ref "IC8") (pin "L8") (pinfunction "USB_OTG1_DP_L8") (pintype "bidirectional"))
    )
    (net (code "129") (name "/VBUS") (class "Default")
      (node (ref "C88") (pin "1") (pinfunction "1_1") (pintype "passive"))
      (node (ref "C95") (pin "2") (pinfunction "2_2") (pintype "passive"))
      (node (ref "IC8") (pin "N6") (pinfunction "USB_OTG1_VBUS_N6") (pintype "bidirectional"))
    )
    (net (code "130") (name "/VCC_SOC") (class "Default")
      (node (ref "C100") (pin "2") (pinfunction "2_2") (pintype "passive"))
      (node (ref "C103") (pin "2") (pinfunction "2_2") (pintype "passive"))
      (node (ref "C34") (pin "1") (pinfunction "1_1") (pintype "passive"))
      (node (ref "C38") (pin "1") (pinfunction "1_1") (pintype "passive"))
      (node (ref "C45") (pin "1") (pinfunction "1_1") (pintype "passive"))
      (node (ref "C46") (pin "2") (pinfunction "2_2") (pintype "passive"))
      (node (ref "C47") (pin "1") (pinfunction "1_1") (pintype "passive"))
      (node (ref "C48") (pin "1") (pinfunction "1_1") (pintype "passive"))
      (node (ref "C49") (pin "2") (pinfunction "2_2") (pintype "passive"))
      (node (ref "C87") (pin "2") (pinfunction "2_2") (pintype "passive"))
      (node (ref "C94") (pin "2") (pinfunction "2_2") (pintype "passive"))
      (node (ref "C97") (pin "2") (pinfunction "2_2") (pintype "passive"))
      (node (ref "C98") (pin "2") (pinfunction "2_2") (pintype "passive"))
      (node (ref "IC8") (pin "F6") (pinfunction "VDD_SOC_IN_1_F6") (pintype "bidirectional"))
      (node (ref "IC8") (pin "F7") (pinfunction "VDD_SOC_IN_2_F7") (pintype "bidirectional"))
      (node (ref "IC8") (pin "F8") (pinfunction "VDD_SOC_IN_3_F8") (pintype "bidirectional"))
      (node (ref "IC8") (pin "F9") (pinfunction "VDD_SOC_IN_4_F9") (pintype "bidirectional"))
      (node (ref "IC8") (pin "G6") (pinfunction "VDD_SOC_IN_5_G6") (pintype "bidirectional"))
      (node (ref "IC8") (pin "G9") (pinfunction "VDD_SOC_IN_6_G9") (pintype "bidirectional"))
      (node (ref "IC8") (pin "H6") (pinfunction "VDD_SOC_IN_7_H6") (pintype "bidirectional"))
      (node (ref "IC8") (pin "H9") (pinfunction "VDD_SOC_IN_8_H9") (pintype "bidirectional"))
      (node (ref "IC8") (pin "J5") (pinfunction "DCDC_SENSE_J5") (pintype "bidirectional"))
      (node (ref "IC8") (pin "J9") (pinfunction "VDD_SOC_IN_9_J9") (pintype "bidirectional"))
      (node (ref "L5") (pin "1") (pinfunction "1_1") (pintype "passive"))
    )
    (net (code "131") (name "/VDDA_ADC_3P3") (class "Default")
      (node (ref "C59") (pin "1") (pinfunction "1_1") (pintype "passive"))
      (node (ref "C60") (pin "2") (pinfunction "2_2") (pintype "passive"))
      (node (ref "C61") (pin "2") (pinfunction "2_2") (pintype "passive"))
      (node (ref "IC8") (pin "N14") (pinfunction "VDDA_ADC_3P3_N14") (pintype "bidirectional"))
      (node (ref "L6") (pin "1") (pinfunction "1_1") (pintype "passive"))
    )
    (net (code "132") (name "/VDD_HIGH_CAP") (class "Default")
      (node (ref "C101") (pin "2") (pinfunction "2_2") (pintype "passive"))
      (node (ref "C102") (pin "1") (pinfunction "1_1") (pintype "passive"))
      (node (ref "IC8") (pin "P8") (pinfunction "VDD_HIGH_CAP_P8") (pintype "bidirectional"))
    )
    (net (code "133") (name "/VDD_SNVS_CAP") (class "Default")
      (node (ref "C70") (pin "1") (pinfunction "1_1") (pintype "passive"))
      (node (ref "IC8") (pin "M10") (pinfunction "VDD_SNVS_CAP_M10") (pintype "bidirectional"))
    )
    (net (code "134") (name "/VDD_USB_CAP") (class "Default")
      (node (ref "C71") (pin "1") (pinfunction "1_1") (pintype "passive"))
      (node (ref "C72") (pin "2") (pinfunction "2_2") (pintype "passive"))
      (node (ref "C73") (pin "2") (pinfunction "2_2") (pintype "passive"))
      (node (ref "IC8") (pin "K8") (pinfunction "VDD_USB_CAP_K8") (pintype "bidirectional"))
    )
    (net (code "135") (name "/WAKEUP") (class "Default")
      (node (ref "IC8") (pin "L6") (pinfunction "WAKEUP_L6") (pintype "bidirectional"))
    )
    (net (code "136") (name "/WIFI_CLK") (class "Default")
      (node (ref "IC8") (pin "M13") (pinfunction "GPIO_AD_B1_09_M13") (pintype "bidirectional"))
    )
    (net (code "137") (name "/WIFI_CMD") (class "Default")
      (node (ref "IC8") (pin "H13") (pinfunction "GPIO_AD_B1_08_H13") (pintype "bidirectional"))
    )
    (net (code "138") (name "/WIFI_D0") (class "Default")
      (node (ref "IC8") (pin "M4") (pinfunction "GPIO_SD_B1_03_M4") (pintype "bidirectional"))
    )
    (net (code "139") (name "/WIFI_D1") (class "Default")
      (node (ref "IC8") (pin "M3") (pinfunction "GPIO_SD_B1_02_M3") (pintype "bidirectional"))
    )
    (net (code "140") (name "/WIFI_D2") (class "Default")
      (node (ref "IC8") (pin "J12") (pinfunction "GPIO_AD_B1_06_J12") (pintype "bidirectional"))
    )
    (net (code "141") (name "/WIFI_D3") (class "Default")
      (node (ref "IC8") (pin "K10") (pinfunction "GPIO_AD_B1_07_K10") (pintype "bidirectional"))
    )
    (net (code "142") (name "/WL_H_WAKE") (class "Default")
      (node (ref "IC8") (pin "E11") (pinfunction "GPIO_B0_15_E11") (pintype "bidirectional"))
    )
    (net (code "143") (name "/WL_REG_ON") (class "Default")
      (node (ref "IC8") (pin "E10") (pinfunction "GPIO_B0_14_E10") (pintype "bidirectional"))
    )
    (net (code "144") (name "/XTALI") (class "Default")
      (node (ref "C106") (pin "1") (pinfunction "1_1") (pintype "passive"))
      (node (ref "IC8") (pin "P11") (pinfunction "XTALI_P11") (pintype "bidirectional"))
      (node (ref "R40") (pin "1") (pinfunction "1_1") (pintype "passive"))
      (node (ref "Y2") (pin "3") (pinfunction "CRYSTAL_2_3") (pintype "bidirectional"))
    )
    (net (code "145") (name "/XTALO") (class "Default")
      (node (ref "C105") (pin "1") (pinfunction "1_1") (pintype "passive"))
      (node (ref "IC8") (pin "N11") (pinfunction "XTALO_N11") (pintype "bidirectional"))
      (node (ref "Y2") (pin "1") (pinfunction "CRYSTAL_1_1") (pintype "bidirectional"))
    )
    (net (code "146") (name "GND") (class "Default")
      (node (ref "C100") (pin "1") (pinfunction "1_1") (pintype "passive"))
      (node (ref "C101") (pin "1") (pinfunction "1_1") (pintype "passive"))
      (node (ref "C102") (pin "2") (pinfunction "2_2") (pintype "passive"))
      (node (ref "C103") (pin "1") (pinfunction "1_1") (pintype "passive"))
      (node (ref "C104") (pin "1") (pinfunction "1_1") (pintype "passive"))
      (node (ref "C105") (pin "2") (pinfunction "2_2") (pintype "passive"))
      (node (ref "C106") (pin "2") (pinfunction "2_2") (pintype "passive"))
      (node (ref "C107") (pin "2") (pinfunction "2_2") (pintype "passive"))
      (node (ref "C108") (pin "1") (pinfunction "1_1") (pintype "passive"))
      (node (ref "C109") (pin "2") (pinfunction "2_2") (pintype "passive"))
      (node (ref "C25") (pin "1") (pinfunction "1_1") (pintype "passive"))
      (node (ref "C34") (pin "2") (pinfunction "2_2") (pintype "passive"))
      (node (ref "C38") (pin "2") (pinfunction "2_2") (pintype "passive"))
      (node (ref "C41") (pin "1") (pinfunction "1_1") (pintype "passive"))
      (node (ref "C43") (pin "2") (pinfunction "2_2") (pintype "passive"))
      (node (ref "C45") (pin "2") (pinfunction "2_2") (pintype "passive"))
      (node (ref "C46") (pin "1") (pinfunction "1_1") (pintype "passive"))
      (node (ref "C47") (pin "2") (pinfunction "2_2") (pintype "passive"))
      (node (ref "C48") (pin "2") (pinfunction "2_2") (pintype "passive"))
      (node (ref "C49") (pin "1") (pinfunction "1_1") (pintype "passive"))
      (node (ref "C50") (pin "2") (pinfunction "2_2") (pintype "passive"))
      (node (ref "C53") (pin "2") (pinfunction "2_2") (pintype "passive"))
      (node (ref "C54") (pin "2") (pinfunction "2_2") (pintype "passive"))
      (node (ref "C55") (pin "2") (pinfunction "2_2") (pintype "passive"))
      (node (ref "C56") (pin "2") (pinfunction "2_2") (pintype "passive"))
      (node (ref "C57") (pin "1") (pinfunction "1_1") (pintype "passive"))
      (node (ref "C58") (pin "1") (pinfunction "1_1") (pintype "passive"))
      (node (ref "C59") (pin "2") (pinfunction "2_2") (pintype "passive"))
      (node (ref "C60") (pin "1") (pinfunction "1_1") (pintype "passive"))
      (node (ref "C61") (pin "1") (pinfunction "1_1") (pintype "passive"))
      (node (ref "C62") (pin "2") (pinfunction "2_2") (pintype "passive"))
      (node (ref "C63") (pin "2") (pinfunction "2_2") (pintype "passive"))
      (node (ref "C64") (pin "2") (pinfunction "2_2") (pintype "passive"))
      (node (ref "C66") (pin "1") (pinfunction "1_1") (pintype "passive"))
      (node (ref "C67") (pin "2") (pinfunction "2_2") (pintype "passive"))
      (node (ref "C68") (pin "1") (pinfunction "1_1") (pintype "passive"))
      (node (ref "C69") (pin "2") (pinfunction "2_2") (pintype "passive"))
      (node (ref "C70") (pin "2") (pinfunction "2_2") (pintype "passive"))
      (node (ref "C71") (pin "2") (pinfunction "2_2") (pintype "passive"))
      (node (ref "C72") (pin "1") (pinfunction "1_1") (pintype "passive"))
      (node (ref "C73") (pin "1") (pinfunction "1_1") (pintype "passive"))
      (node (ref "C79") (pin "2") (pinfunction "2_2") (pintype "passive"))
      (node (ref "C80") (pin "2") (pinfunction "2_2") (pintype "passive"))
      (node (ref "C86") (pin "1") (pinfunction "1_1") (pintype "passive"))
      (node (ref "C87") (pin "1") (pinfunction "1_1") (pintype "passive"))
      (node (ref "C88") (pin "2") (pinfunction "2_2") (pintype "passive"))
      (node (ref "C94") (pin "1") (pinfunction "1_1") (pintype "passive"))
      (node (ref "C95") (pin "1") (pinfunction "1_1") (pintype "passive"))
      (node (ref "C97") (pin "1") (pinfunction "1_1") (pintype "passive"))
      (node (ref "C98") (pin "1") (pinfunction "1_1") (pintype "passive"))
      (node (ref "C99") (pin "1") (pinfunction "1_1") (pintype "passive"))
      (node (ref "IC8") (pin "A1") (pinfunction "VSS_1_A1") (pintype "bidirectional"))
      (node (ref "IC8") (pin "A14") (pinfunction "VSS_2_A14") (pintype "bidirectional"))
      (node (ref "IC8") (pin "B10") (pinfunction "VSS_4_B10") (pintype "bidirectional"))
      (node (ref "IC8") (pin "B5") (pinfunction "VSS_3_B5") (pintype "bidirectional"))
      (node (ref "IC8") (pin "E13") (pinfunction "VSS_6_E13") (pintype "bidirectional"))
      (node (ref "IC8") (pin "E2") (pinfunction "VSS_5_E2") (pintype "bidirectional"))
      (node (ref "IC8") (pin "G7") (pinfunction "VSS_7_G7") (pintype "bidirectional"))
      (node (ref "IC8") (pin "G8") (pinfunction "VSS_8_G8") (pintype "bidirectional"))
      (node (ref "IC8") (pin "H7") (pinfunction "VSS_9_H7") (pintype "bidirectional"))
      (node (ref "IC8") (pin "H8") (pinfunction "VSS_10_H8") (pintype "bidirectional"))
      (node (ref "IC8") (pin "J7") (pinfunction "VSS_11_J7") (pintype "bidirectional"))
      (node (ref "IC8") (pin "J8") (pinfunction "VSS_12_J8") (pintype "bidirectional"))
      (node (ref "IC8") (pin "K13") (pinfunction "VSS_14_K13") (pintype "bidirectional"))
      (node (ref "IC8") (pin "K2") (pinfunction "VSS_13_K2") (pintype "bidirectional"))
      (node (ref "IC8") (pin "K6") (pinfunction "TEST_MODE_K6") (pintype "bidirectional"))
      (node (ref "IC8") (pin "K9") (pinfunction "NGND_KEL0_K9") (pintype "bidirectional"))
      (node (ref "IC8") (pin "L9") (pinfunction "VSS_15_L9") (pintype "bidirectional"))
      (node (ref "IC8") (pin "N1") (pinfunction "DCDC_GND_1_N1") (pintype "bidirectional"))
      (node (ref "IC8") (pin "N2") (pinfunction "DCDC_GND_2_N2") (pintype "bidirectional"))
      (node (ref "IC8") (pin "N5") (pinfunction "VSS_16_N5") (pintype "bidirectional"))
      (node (ref "IC8") (pin "N8") (pinfunction "VSS_17_N8") (pintype "bidirectional"))
      (node (ref "IC8") (pin "P1") (pinfunction "VSS_18_P1") (pintype "bidirectional"))
      (node (ref "IC8") (pin "P14") (pinfunction "VSS_19_P14") (pintype "bidirectional"))
      (node (ref "R40") (pin "2") (pinfunction "2_2") (pintype "passive"))
      (node (ref "S1") (pin "1") (pinfunction "NO_1") (pintype "passive"))
      (node (ref "S1") (pin "5") (pinfunction "NO_5") (pintype "passive"))
      (node (ref "S2") (pin "1") (pinfunction "NO_1") (pintype "passive"))
      (node (ref "S2") (pin "5") (pinfunction "NO_5") (pintype "passive"))
      (node (ref "Y2") (pin "2") (pinfunction "NC_1_2") (pintype "bidirectional"))
      (node (ref "Y2") (pin "4") (pinfunction "NC_2_4") (pintype "bidirectional"))
    )
    (net (code "147") (name "VCC") (class "Default")
      (node (ref "C108") (pin "2") (pinfunction "2_2") (pintype "passive"))
      (node (ref "C109") (pin "1") (pinfunction "1_1") (pintype "passive"))
      (node (ref "C41") (pin "2") (pinfunction "2_2") (pintype "passive"))
      (node (ref "C43") (pin "1") (pinfunction "1_1") (pintype "passive"))
      (node (ref "C50") (pin "1") (pinfunction "1_1") (pintype "passive"))
      (node (ref "C53") (pin "1") (pinfunction "1_1") (pintype "passive"))
      (node (ref "C54") (pin "1") (pinfunction "1_1") (pintype "passive"))
      (node (ref "C55") (pin "1") (pinfunction "1_1") (pintype "passive"))
      (node (ref "C56") (pin "1") (pinfunction "1_1") (pintype "passive"))
      (node (ref "C57") (pin "2") (pinfunction "2_2") (pintype "passive"))
      (node (ref "C58") (pin "2") (pinfunction "2_2") (pintype "passive"))
      (node (ref "C64") (pin "1") (pinfunction "1_1") (pintype "passive"))
      (node (ref "C66") (pin "2") (pinfunction "2_2") (pintype "passive"))
      (node (ref "C67") (pin "1") (pinfunction "1_1") (pintype "passive"))
      (node (ref "C68") (pin "2") (pinfunction "2_2") (pintype "passive"))
      (node (ref "C86") (pin "2") (pinfunction "2_2") (pintype "passive"))
      (node (ref "C99") (pin "2") (pinfunction "2_2") (pintype "passive"))
      (node (ref "IC8") (pin "E6") (pinfunction "NVCC_EMC_1_E6") (pintype "bidirectional"))
      (node (ref "IC8") (pin "E9") (pinfunction "NVCC_GPIO_1_E9") (pintype "bidirectional"))
      (node (ref "IC8") (pin "F10") (pinfunction "NVCC_GPIO_2_F10") (pintype "bidirectional"))
      (node (ref "IC8") (pin "F5") (pinfunction "NVCC_EMC_2_F5") (pintype "bidirectional"))
      (node (ref "IC8") (pin "J10") (pinfunction "NVCC_GPIO_3_J10") (pintype "bidirectional"))
      (node (ref "IC8") (pin "J6") (pinfunction "NVCC_SD0_J6") (pintype "bidirectional"))
      (node (ref "IC8") (pin "K4") (pinfunction "DCDC_IN_Q_K4") (pintype "bidirectional"))
      (node (ref "IC8") (pin "K5") (pinfunction "NVCC_SD1_K5") (pintype "bidirectional"))
      (node (ref "IC8") (pin "L1") (pinfunction "DCDC_IN_1_L1") (pintype "bidirectional"))
      (node (ref "IC8") (pin "L2") (pinfunction "DCDC_IN_2_L2") (pintype "bidirectional"))
      (node (ref "IC8") (pin "P12") (pinfunction "VDD_HIGH_IN_P12") (pintype "bidirectional"))
      (node (ref "L6") (pin "2") (pinfunction "2_2") (pintype "passive"))
      (node (ref "R32") (pin "2") (pinfunction "2_2") (pintype "passive"))
      (node (ref "R33") (pin "1") (pinfunction "1_1") (pintype "passive"))
      (node (ref "R67") (pin "2") (pinfunction "2_2") (pintype "passive"))
    )
    (net (code "148") (name "VDD_SNVS_CPU") (class "Default")
      (node (ref "C69") (pin "1") (pinfunction "1_1") (pintype "passive"))
      (node (ref "IC8") (pin "M9") (pinfunction "VDD_SNVS_IN_M9") (pintype "bidirectional"))
    )
    (net (code "149") (name "unconnected-(IC8-CCM_CLK1_N-PadP13)") (class "Default")
      (node (ref "IC8") (pin "P13") (pinfunction "CCM_CLK1_N_P13") (pintype "bidirectional"))
    )
    (net (code "150") (name "unconnected-(IC8-CCM_CLK1_P-PadN13)") (class "Default")
      (node (ref "IC8") (pin "N13") (pinfunction "CCM_CLK1_P_N13") (pintype "bidirectional"))
    )
    (net (code "151") (name "unconnected-(IC8-GPANAIO-PadN10)") (class "Default")
      (node (ref "IC8") (pin "N10") (pinfunction "GPANAIO_N10") (pintype "bidirectional"))
    )
    (net (code "152") (name "unconnected-(IC8-GPIO_EMC_39-PadB7)") (class "Default")
      (node (ref "IC8") (pin "B7") (pinfunction "GPIO_EMC_39_B7") (pintype "bidirectional"))
    )
    (net (code "153") (name "unconnected-(IC8-GPIO_SD_B1_05-PadN3)") (class "Default")
      (node (ref "IC8") (pin "N3") (pinfunction "GPIO_SD_B1_05_N3") (pintype "bidirectional"))
    )
    (net (code "154") (name "unconnected-(IC8-USB_OTG1_CHD_B-PadN12)") (class "Default")
      (node (ref "IC8") (pin "N12") (pinfunction "USB_OTG1_CHD_B_N12") (pintype "bidirectional"))
    )
    (net (code "155") (name "unconnected-(IC8-USB_OTG2_DN-PadN7)") (class "Default")
      (node (ref "IC8") (pin "N7") (pinfunction "USB_OTG2_DN_N7") (pintype "bidirectional"))
    )
    (net (code "156") (name "unconnected-(IC8-USB_OTG2_DP-PadP7)") (class "Default")
      (node (ref "IC8") (pin "P7") (pinfunction "USB_OTG2_DP_P7") (pintype "bidirectional"))
    )
    (net (code "157") (name "unconnected-(IC8-USB_OTG2_VBUS-PadP6)") (class "Default")
      (node (ref "IC8") (pin "P6") (pinfunction "USB_OTG2_VBUS_P6") (pintype "bidirectional"))
    )
  )
)
